# 12V.net
KiCad netlist of a schematic drawn in Altium Designer
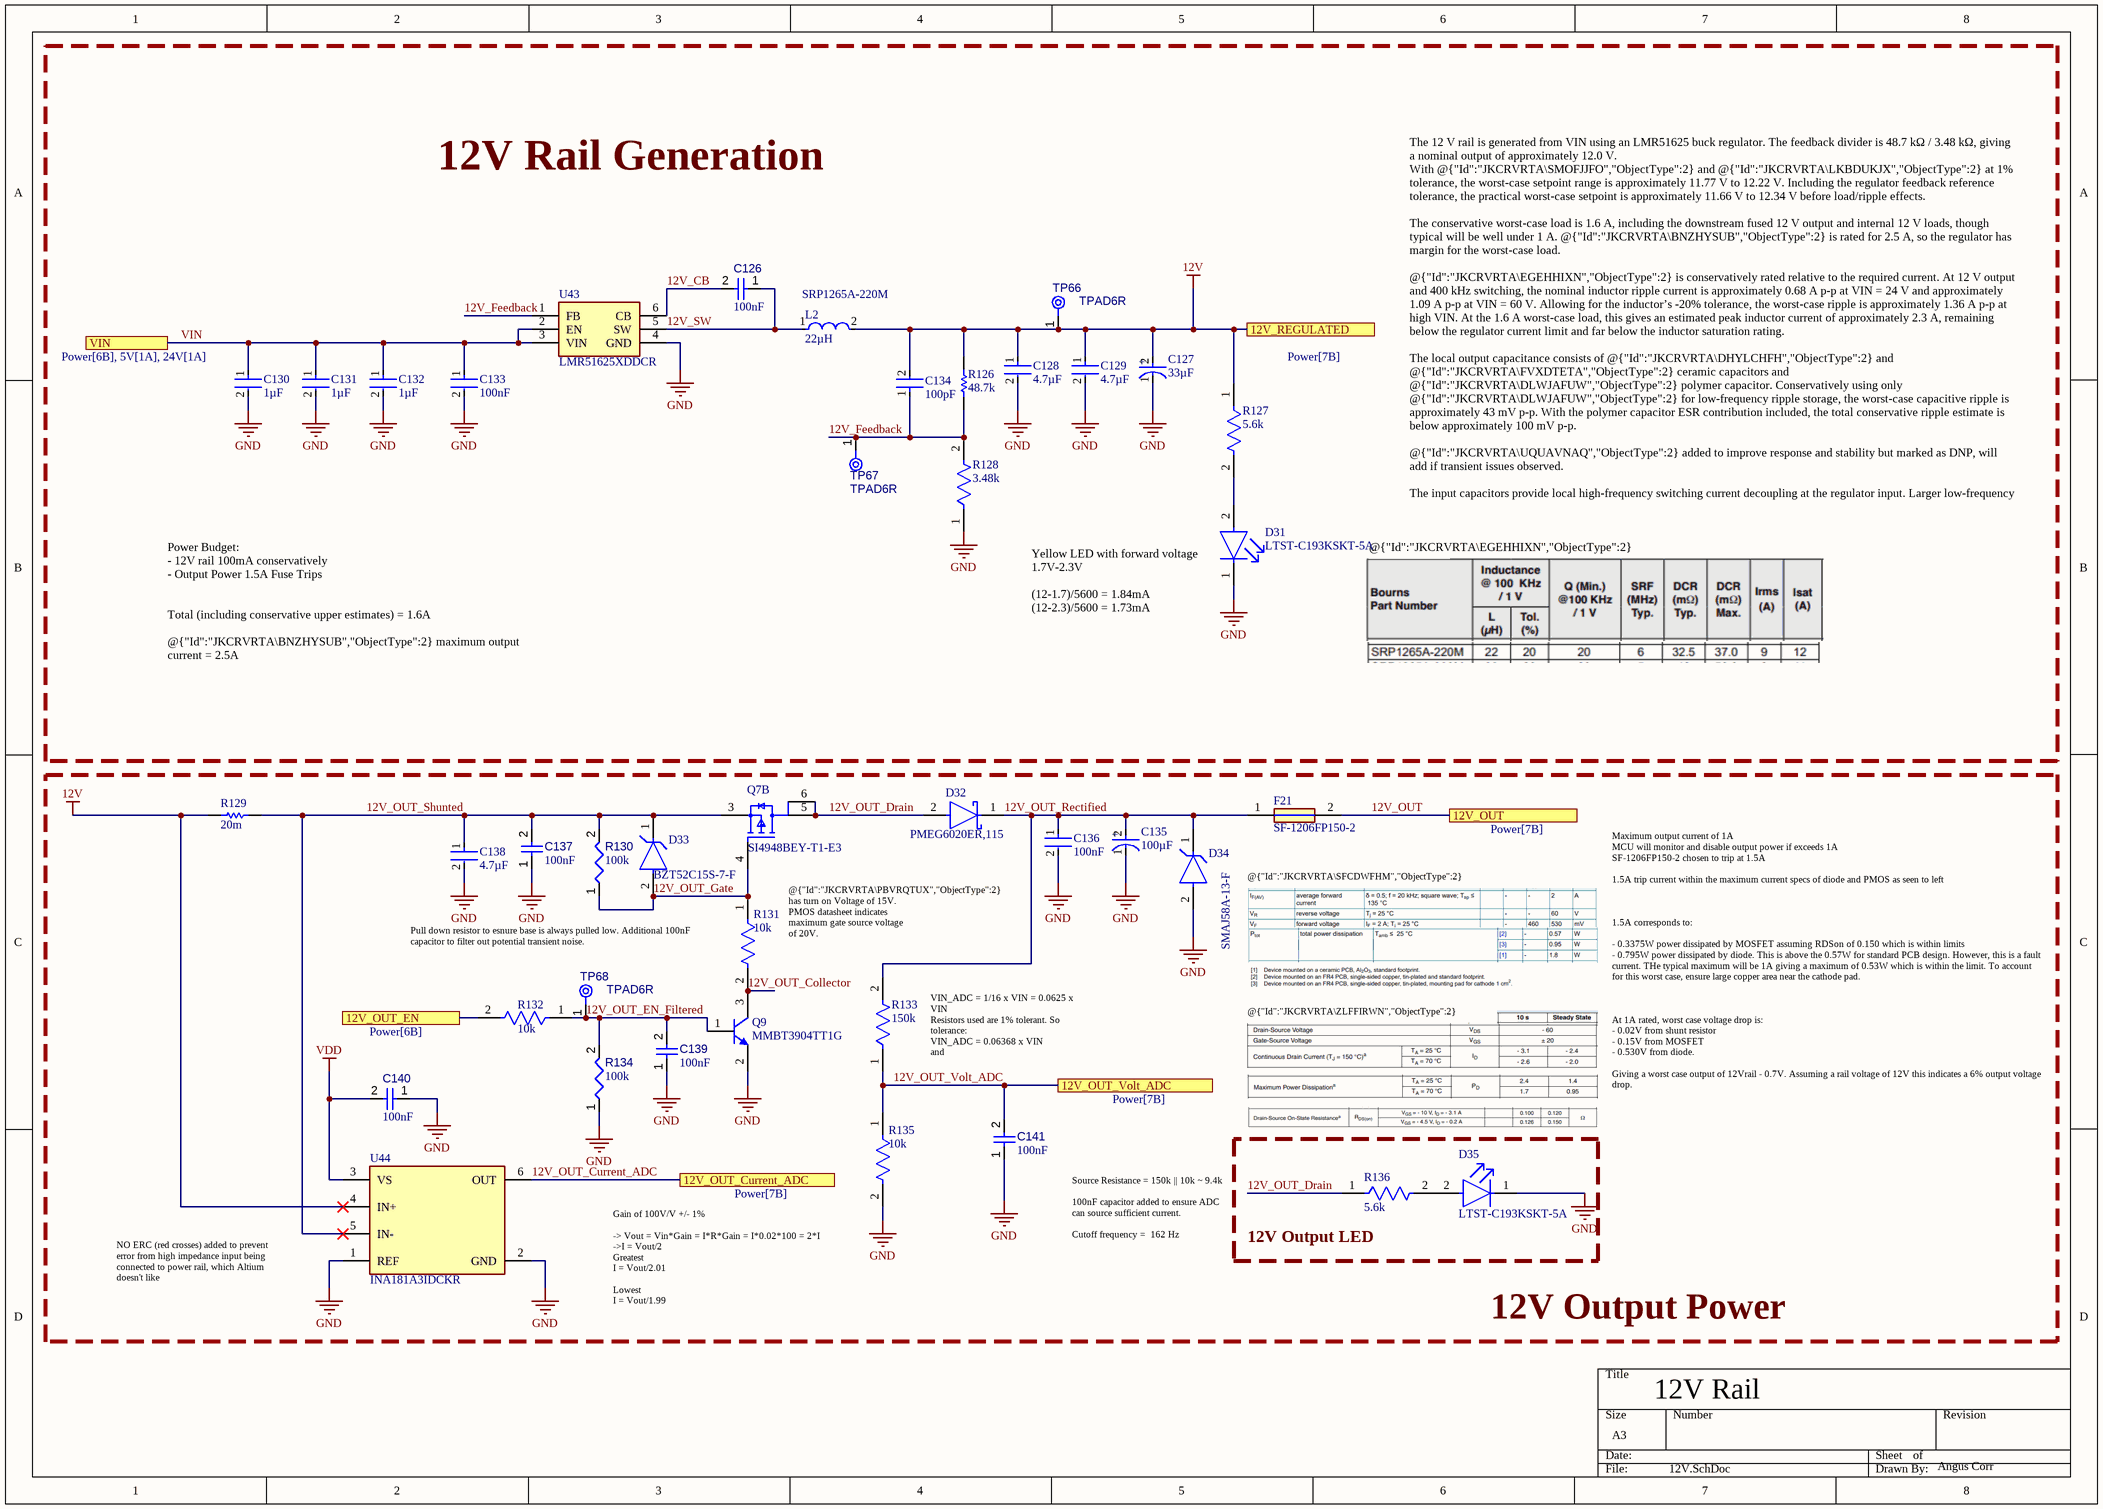
[diagram p0:  12V.SchDoc]

(export (version "E")
  (design (tool "Eeschema 10.0.6"))
  (components
    (comp (ref "C126")
      (value "100nF")
      (footprint "CAPC1608X90X40NL10T20")
      (description "Chip Capacitor, 100 nF, +/- 10%, 50 V, 0603 (1608 Metric)")
      (fields (field (name "TOLERANCE") "10%") (field (name "Comment") "Capacitor 100 nF +/-10% 50 V 0603"))
      (libsource (lib "HIL RIG FYP") (part "CAP-NP-2"))
    )
    (comp (ref "C127")
      (value "33µF")
      (footprint "FP-EEH-D8-MFG")
      (description "Cap Aluminum 33uF 50V 20% (6.3 X 7.7mm) SMD 0.04 Ohm 1600mA 5000 hr 105°C Embossed T/R")
      (fields (field (name "TOLERANCE") "20%") (field (name "Comment") "EEHZA1H330XP"))
      (libsource (lib "HIL RIG FYP") (part "a00bbbee19879c290e62620ae7e47b1"))
    )
    (comp (ref "C128")
      (value "4.7µF")
      (footprint "FP-GRM21B-0_2-e0_2_0_7-MFG")
      (description "50V 4.7uF X7R ±10% 0805 Multilayer Ceramic Capacitors MLCC - SMD/SMT ROHS")
      (fields (field (name "TOLERANCE") "10%") (field (name "Comment") "GRM21BZ71H475KE15L"))
      (libsource (lib "HIL RIG FYP") (part "b4654b650e69147ec39a6b967a45e02"))
    )
    (comp (ref "C129")
      (value "4.7µF")
      (footprint "FP-GRM21B-0_2-e0_2_0_7-MFG")
      (description "50V 4.7uF X7R ±10% 0805 Multilayer Ceramic Capacitors MLCC - SMD/SMT ROHS")
      (fields (field (name "TOLERANCE") "10%") (field (name "Comment") "GRM21BZ71H475KE15L"))
      (libsource (lib "HIL RIG FYP") (part "b4654b650e69147ec39a6b967a45e02"))
    )
    (comp (ref "C130")
      (value "1µF")
      (footprint "FP-GRJ21B-0_35-MFG")
      (description "100V 1uF X7S ±10% 0805 Multilayer Ceramic Capacitors MLCC - SMD/SMT ROHS")
      (fields (field (name "TOLERANCE") "10%") (field (name "Comment") "GRJ21BC72A105KE11L"))
      (libsource (lib "HIL RIG FYP") (part "b4654b650e69147ec39a6b967a45e02"))
    )
    (comp (ref "C131")
      (value "1µF")
      (footprint "FP-GRJ21B-0_35-MFG")
      (description "100V 1uF X7S ±10% 0805 Multilayer Ceramic Capacitors MLCC - SMD/SMT ROHS")
      (fields (field (name "TOLERANCE") "10%") (field (name "Comment") "GRJ21BC72A105KE11L"))
      (libsource (lib "HIL RIG FYP") (part "b4654b650e69147ec39a6b967a45e02"))
    )
    (comp (ref "C132")
      (value "1µF")
      (footprint "FP-GRJ21B-0_35-MFG")
      (description "100V 1uF X7S ±10% 0805 Multilayer Ceramic Capacitors MLCC - SMD/SMT ROHS")
      (fields (field (name "TOLERANCE") "10%") (field (name "Comment") "GRJ21BC72A105KE11L"))
      (libsource (lib "HIL RIG FYP") (part "b4654b650e69147ec39a6b967a45e02"))
    )
    (comp (ref "C133")
      (value "100nF")
      (footprint "FP-GRM31C-0_2-e0_3_0_8-IPC_C")
      (description "100V 100nF C0G ±5% 1206 Multilayer Ceramic Capacitors MLCC - SMD/SMT ROHS")
      (fields (field (name "TOLERANCE") "5%") (field (name "Comment") "GRM31C5C2A104JA01L"))
      (libsource (lib "HIL RIG FYP") (part "02cd4be3c70576c341d710602a673aa"))
    )
    (comp (ref "C134")
      (value "100pF")
      (footprint "FP-C0603C-CF-IPC_B")
      (description "Multilayer Ceramic Capacitors MLCC - SMD/SMT 50V 100pF X8R 0603 1%")
      (fields (field (name "Comment") "C0603C101F5HACTU"))
      (libsource (lib "HIL RIG FYP") (part "b4654b650e69147ec39a6b967a45e02"))
    )
    (comp (ref "C135")
      (value "100µF")
      (footprint "FP-MVYAKE0-MFG")
      (description "Cap Aluminum 100uF 100V 20% (12.5 X 13.5mm) SMD 450mA 5000h 105°C T/R")
      (fields (field (name "TOLERANCE") "20%") (field (name "Comment") "EMVY101ARA101MKE0S"))
      (libsource (lib "HIL RIG FYP") (part "203bc49f2ac43e59fd269a8c329ed05"))
    )
    (comp (ref "C136")
      (value "100nF")
      (footprint "FP-GRM31C-0_2-e0_3_0_8-IPC_C")
      (description "100V 100nF C0G ±5% 1206 Multilayer Ceramic Capacitors MLCC - SMD/SMT ROHS")
      (fields (field (name "TOLERANCE") "5%") (field (name "Comment") "GRM31C5C2A104JA01L"))
      (libsource (lib "HIL RIG FYP") (part "02cd4be3c70576c341d710602a673aa"))
    )
    (comp (ref "C137")
      (value "100nF")
      (footprint "CAPC1608X90X40NL10T20")
      (description "Chip Capacitor, 100 nF, +/- 10%, 50 V, 0603 (1608 Metric)")
      (fields (field (name "TOLERANCE") "10%") (field (name "Comment") "Capacitor 100 nF +/-10% 50 V 0603"))
      (libsource (lib "HIL RIG FYP") (part "CAP-NP-2"))
    )
    (comp (ref "C138")
      (value "4.7µF")
      (footprint "FP-GRM21B-0_2-e0_2_0_7-MFG")
      (description "50V 4.7uF X7R ±10% 0805 Multilayer Ceramic Capacitors MLCC - SMD/SMT ROHS")
      (fields (field (name "TOLERANCE") "10%") (field (name "Comment") "GRM21BZ71H475KE15L"))
      (libsource (lib "HIL RIG FYP") (part "b4654b650e69147ec39a6b967a45e02"))
    )
    (comp (ref "C139")
      (value "100nF")
      (footprint "CAPC1608X90X40NL10T20")
      (description "Chip Capacitor, 100 nF, +/- 10%, 50 V, 0603 (1608 Metric)")
      (fields (field (name "TOLERANCE") "10%") (field (name "Comment") "Capacitor 100 nF +/-10% 50 V 0603"))
      (libsource (lib "HIL RIG FYP") (part "CAP-NP-2"))
    )
    (comp (ref "C140")
      (value "100nF")
      (footprint "CAPC1608X90X40NL10T20")
      (description "Chip Capacitor, 100 nF, +/- 10%, 50 V, 0603 (1608 Metric)")
      (fields (field (name "TOLERANCE") "10%") (field (name "Comment") "Capacitor 100 nF +/-10% 50 V 0603"))
      (libsource (lib "HIL RIG FYP") (part "CAP-NP-2"))
    )
    (comp (ref "C141")
      (value "100nF")
      (footprint "CAPC1608X90X40NL10T20")
      (description "Chip Capacitor, 100 nF, +/- 10%, 50 V, 0603 (1608 Metric)")
      (fields (field (name "TOLERANCE") "10%") (field (name "Comment") "Capacitor 100 nF +/-10% 50 V 0603"))
      (libsource (lib "HIL RIG FYP") (part "CAP-NP-2"))
    )
    (comp (ref "D31")
      (value "LTST-C193KSKT-5A")
      (footprint "FP-LTST-C193KGKT-5A-MFG")
      (description "LED yellow 0603 wavelength 587~594.5nm light intensity 7.1~45mcd Front Mounting")
      (libsource (lib "HIL RIG FYP") (part "8706943c75ba83719d021d2fdc84c58"))
    )
    (comp (ref "D32")
      (value "PMEG6020ER,115")
      (footprint "FP-SOD123W-MFG")
      (description "PMEG6020 Series 60 V 2 A SMT Llow VF MEGA Schottky Barrier Rectifier - SOD-123W")
      (libsource (lib "HIL RIG FYP") (part "1d6ec82d83fb6aee721767c19dac4b9"))
    )
    (comp (ref "D33")
      (value "BZT52C15S-7-F")
      (footprint "FP-SOD323-IPC_A")
      (description "BZT52C15S Series 200 mW 15 V 10 mA Surface Mount Zener Diode - SOD-323")
      (libsource (lib "HIL RIG FYP") (part "f813f71cba58e380607f5dd3caf9714"))
    )
    (comp (ref "D34")
      (value "SMAJ58A-13-F")
      (footprint "FP-SMA-MFG")
      (description "SMAJ Series 58 V 400 W SMT Uni-Directional TVS Diode - DO-214AC")
      (libsource (lib "HIL RIG FYP") (part "f813f71cba58e380607f5dd3caf9714"))
    )
    (comp (ref "D35")
      (value "LTST-C193KSKT-5A")
      (footprint "FP-LTST-C193KGKT-5A-MFG")
      (description "LED yellow 0603 wavelength 587~594.5nm light intensity 7.1~45mcd Front Mounting")
      (libsource (lib "HIL RIG FYP") (part "8706943c75ba83719d021d2fdc84c58"))
    )
    (comp (ref "F21")
      (value "SF-1206FP150-2")
      (footprint "FUSC3116X70N")
      (description "Surface Mount Fuses 1.5A Fast Acting 1206 Singlfuse")
      (fields (field (name "MOUSER PART NUMBER") "652-SF-1206FP150-2"))
      (libsource (lib "HIL RIG FYP") (part "SF-1206FP150-2"))
    )
    (comp (ref "L2")
      (value "22µH")
      (footprint "FP-SRP1265A-MFG")
      (fields (field (name "TOLERANCE") "20%") (field (name "Comment") "SRP1265A-220M"))
      (libsource (lib "HIL RIG FYP") (part "725321dda6339637d4d059423bc1c3c"))
    )
    (comp (ref "Q7")
      (value "SI4948BEY-T1-E3")
      (footprint "FP-C-06527-IPC_B")
      (description "Dual P-Channel 60 V 0.12 Ohms Surface Mount Power Mosfet - SOIC-8")
      (libsource (lib "HIL RIG FYP") (part "8dc75c867fb8938c255332086adbf49"))
    )
    (comp (ref "Q9")
      (value "MMBT3904TT1G")
      (footprint "ONSC-SC-75-3-463-01_V")
      (description "on Semi MMBT3904TT1G NPN Bipolar Transistor, 0.2 A, 40 V, 3-PIN SOT-416")
      (libsource (lib "HIL RIG FYP") (part "ONSC-NPN-B1E2C3-3"))
    )
    (comp (ref "R126")
      (value "48.7k")
      (footprint "RESC1608X55X25ML10T15")
      (description "Res Thick Film 0603 48.7K Ohm 1% 0.1W(1/10W) ±100ppm/C Pad SMD T/R")
      (fields (field (name "TOLERANCE") "1%") (field (name "Comment") "RC0603FR-0748K7L"))
      (libsource (lib "HIL RIG FYP") (part "RES"))
    )
    (comp (ref "R127")
      (value "5.6k")
      (footprint "FP-RT0603-IPC_C")
      (description "Fixed Resistor, Thin Film, 0.1W, 5600ohm, 75V, 1% +/-Tol, 50ppm/Cel, Surface Mount, 0603")
      (fields (field (name "TOLERANCE") "1%") (field (name "Comment") "RT0603FRE075K6L"))
      (libsource (lib "HIL RIG FYP") (part "1029c3af85768c4190bb7ad29bc67b5"))
    )
    (comp (ref "R128")
      (value "3.48k")
      (footprint "FP-AC0603-IPC_C")
      (description "Res Thick Film 0603 3.48K Ohm 1% 0.1W(1/10W) ±100ppm/C Pad SMD T/R Automotive AEC-Q200")
      (fields (field (name "TOLERANCE") "1%") (field (name "Comment") "AC0603FR-073K48L"))
      (libsource (lib "HIL RIG FYP") (part "1029c3af85768c4190bb7ad29bc67b5"))
    )
    (comp (ref "R129")
      (value "20m")
      (footprint "RESC3216X89X51NL25T25")
      (description "Res Metal Strip 1206 0.02 Ohm 1% 1/4W ±75ppm/°C Molded SMD SMD Embossed Plastic T/R")
      (fields (field (name "TOLERANCE") "1%") (field (name "Comment") "WSL1206R0200FEA"))
      (libsource (lib "HIL RIG FYP") (part "RES"))
    )
    (comp (ref "R130")
      (value "100k")
      (footprint "FP-AC0603-IPC_C")
      (description "Res Thick Film 0603 100K Ohm 1% 0.1W(1/10W) ±100ppm/C Pad SMD T/R Automotive")
      (fields (field (name "TOLERANCE") "1%") (field (name "Comment") "AC0603FR-07100KL"))
      (libsource (lib "HIL RIG FYP") (part "RES-2"))
    )
    (comp (ref "R131")
      (value "10k")
      (footprint "FP-RT0603-IPC_C")
      (description "Res Thin Film 0603 10K Ohm 0.1% 1/10W ¦25ppm/¦C SMD Paper T/R")
      (fields (field (name "TOLERANCE") "0.1%") (field (name "Comment") "RT0603BRD0710KL"))
      (libsource (lib "HIL RIG FYP") (part "1029c3af85768c4190bb7ad29bc67b5"))
    )
    (comp (ref "R132")
      (value "10k")
      (footprint "FP-RT0603-IPC_C")
      (description "Res Thin Film 0603 10K Ohm 0.1% 1/10W ¦25ppm/¦C SMD Paper T/R")
      (fields (field (name "TOLERANCE") "0.1%") (field (name "Comment") "RT0603BRD0710KL"))
      (libsource (lib "HIL RIG FYP") (part "1029c3af85768c4190bb7ad29bc67b5"))
    )
    (comp (ref "R133")
      (value "150k")
      (footprint "FP-CRGCQ0603-IPC_A")
      (description "Res Thick Film 0603 150K Ohm 1% 0.1W(1/10W) ±100ppm/C Pad SMD Automotive T/R")
      (fields (field (name "TOLERANCE") "1%") (field (name "Comment") "CRGCQ0603F150K"))
      (libsource (lib "HIL RIG FYP") (part "1029c3af85768c4190bb7ad29bc67b5"))
    )
    (comp (ref "R134")
      (value "100k")
      (footprint "FP-AC0603-IPC_C")
      (description "Res Thick Film 0603 100K Ohm 1% 0.1W(1/10W) ±100ppm/C Pad SMD T/R Automotive")
      (fields (field (name "TOLERANCE") "1%") (field (name "Comment") "AC0603FR-07100KL"))
      (libsource (lib "HIL RIG FYP") (part "RES-2"))
    )
    (comp (ref "R135")
      (value "10k")
      (footprint "FP-RT0603-IPC_C")
      (description "Res Thin Film 0603 10K Ohm 0.1% 1/10W ¦25ppm/¦C SMD Paper T/R")
      (fields (field (name "TOLERANCE") "0.1%") (field (name "Comment") "RT0603BRD0710KL"))
      (libsource (lib "HIL RIG FYP") (part "1029c3af85768c4190bb7ad29bc67b5"))
    )
    (comp (ref "R136")
      (value "5.6k")
      (footprint "FP-RT0603-IPC_C")
      (description "Fixed Resistor, Thin Film, 0.1W, 5600ohm, 75V, 1% +/-Tol, 50ppm/Cel, Surface Mount, 0603")
      (fields (field (name "TOLERANCE") "1%") (field (name "Comment") "RT0603FRE075K6L"))
      (libsource (lib "HIL RIG FYP") (part "1029c3af85768c4190bb7ad29bc67b5"))
    )
    (comp (ref "TP66")
      (value "TPAD6R")
      (footprint "TP06R")
      (description "0.6mm round")
      (libsource (lib "HIL RIG FYP") (part "CMP-001-0001-4"))
    )
    (comp (ref "TP67")
      (value "TPAD6R")
      (footprint "TP06R")
      (description "0.6mm round")
      (libsource (lib "HIL RIG FYP") (part "CMP-001-0001-4"))
    )
    (comp (ref "TP68")
      (value "TPAD6R")
      (footprint "TP06R")
      (description "0.6mm round")
      (libsource (lib "HIL RIG FYP") (part "CMP-001-0001-4"))
    )
    (comp (ref "U43")
      (value "LMR51625XDDCR")
      (footprint "SOT95P280X110-6N")
      (description "Switching Voltage Regulators SIMPLE SWITCHER synchronous buck converter with 4.3V-to-60V")
      (fields (field (name "MOUSER PART NUMBER") "595-LMR51625XDDCR"))
      (libsource (lib "HIL RIG FYP") (part "LMR51625XDDCR"))
    )
    (comp (ref "U44")
      (value "INA181A3IDCKR")
      (footprint "FP-DCK0006A-IPC_A")
      (description "26-V bi-directional 350-kHz current-sense amplifier 6-SC70 -40 to 125")
      (libsource (lib "HIL RIG FYP") (part "a7b5cee9b6bc60f4871af0ee2c3b109"))
    )
  )
  (nets
    (net (code "1") (name "/12V_CB") (class "Default")
      (node (ref "C126") (pin "2") (pinfunction "2_2") (pintype "passive"))
      (node (ref "U43") (pin "6") (pinfunction "CB_6") (pintype "passive"))
    )
    (net (code "2") (name "/12V_Feedback") (class "Default")
      (node (ref "C134") (pin "1") (pinfunction "1_1") (pintype "passive"))
      (node (ref "R126") (pin "1") (pinfunction "1_1") (pintype "passive"))
      (node (ref "R128") (pin "2") (pinfunction "2_2") (pintype "passive"))
      (node (ref "TP67") (pin "1") (pinfunction "TP_1") (pintype "passive"))
      (node (ref "U43") (pin "1") (pinfunction "FB_1") (pintype "passive"))
    )
    (net (code "3") (name "/12V_OUT") (class "Default")
      (node (ref "F21") (pin "2") (pinfunction "2_2") (pintype "passive"))
    )
    (net (code "4") (name "/12V_OUT_Collector") (class "Default")
      (node (ref "Q9") (pin "3") (pinfunction "C_3") (pintype "passive"))
      (node (ref "R131") (pin "2") (pinfunction "2_2") (pintype "passive"))
    )
    (net (code "5") (name "/12V_OUT_Current_ADC") (class "Default")
      (node (ref "U44") (pin "6") (pinfunction "OUT_6") (pintype "passive"))
    )
    (net (code "6") (name "/12V_OUT_Drain") (class "Default")
      (node (ref "D32") (pin "2") (pinfunction "A_2") (pintype "passive"))
      (node (ref "Q7") (pin "5") (pinfunction "D2_5") (pintype "passive"))
      (node (ref "Q7") (pin "6") (pinfunction "D2_6") (pintype "passive"))
      (node (ref "R136") (pin "1") (pinfunction "1_1") (pintype "passive"))
    )
    (net (code "7") (name "/12V_OUT_EN") (class "Default")
      (node (ref "R132") (pin "2") (pinfunction "2_2") (pintype "passive"))
    )
    (net (code "8") (name "/12V_OUT_EN_Filtered") (class "Default")
      (node (ref "C139") (pin "2") (pinfunction "2_2") (pintype "passive"))
      (node (ref "Q9") (pin "1") (pinfunction "B_1") (pintype "passive"))
      (node (ref "R132") (pin "1") (pinfunction "1_1") (pintype "passive"))
      (node (ref "R134") (pin "2") (pinfunction "2_2") (pintype "passive"))
      (node (ref "TP68") (pin "1") (pinfunction "TP_1") (pintype "passive"))
    )
    (net (code "9") (name "/12V_OUT_Gate") (class "Default")
      (node (ref "D33") (pin "2") (pinfunction "A_2") (pintype "passive"))
      (node (ref "Q7") (pin "4") (pinfunction "G2_4") (pintype "passive"))
      (node (ref "R130") (pin "1") (pinfunction "1_1") (pintype "passive"))
      (node (ref "R131") (pin "1") (pinfunction "1_1") (pintype "passive"))
    )
    (net (code "10") (name "/12V_OUT_Rectified") (class "Default")
      (node (ref "C135") (pin "2") (pinfunction "A_2") (pintype "passive"))
      (node (ref "C136") (pin "1") (pinfunction "1_1") (pintype "passive"))
      (node (ref "D32") (pin "1") (pinfunction "C_1") (pintype "passive"))
      (node (ref "D34") (pin "1") (pinfunction "C_1") (pintype "passive"))
      (node (ref "F21") (pin "1") (pinfunction "1_1") (pintype "passive"))
      (node (ref "R133") (pin "2") (pinfunction "2_2") (pintype "passive"))
    )
    (net (code "11") (name "/12V_OUT_Shunted") (class "Default")
      (node (ref "C137") (pin "2") (pinfunction "2_2") (pintype "passive"))
      (node (ref "C138") (pin "1") (pinfunction "1_1") (pintype "passive"))
      (node (ref "D33") (pin "1") (pinfunction "C_1") (pintype "passive"))
      (node (ref "Q7") (pin "3") (pinfunction "S2_3") (pintype "passive"))
      (node (ref "R129") (pin "2") (pinfunction "2_2") (pintype "passive"))
      (node (ref "R130") (pin "2") (pinfunction "2_2") (pintype "passive"))
      (node (ref "U44") (pin "5") (pinfunction "IN-_5") (pintype "tri_state"))
    )
    (net (code "12") (name "/12V_OUT_Volt_ADC") (class "Default")
      (node (ref "C141") (pin "2") (pinfunction "2_2") (pintype "passive"))
      (node (ref "R133") (pin "1") (pinfunction "1_1") (pintype "passive"))
      (node (ref "R135") (pin "1") (pinfunction "1_1") (pintype "passive"))
    )
    (net (code "13") (name "/12V_SW") (class "Default")
      (node (ref "C126") (pin "1") (pinfunction "1_1") (pintype "passive"))
      (node (ref "L2") (pin "1") (pinfunction "1_1") (pintype "passive"))
      (node (ref "U43") (pin "5") (pinfunction "SW_5") (pintype "passive"))
    )
    (net (code "14") (name "/VIN") (class "Default")
      (node (ref "C130") (pin "1") (pinfunction "1_1") (pintype "passive"))
      (node (ref "C131") (pin "1") (pinfunction "1_1") (pintype "passive"))
      (node (ref "C132") (pin "1") (pinfunction "1_1") (pintype "passive"))
      (node (ref "C133") (pin "1") (pinfunction "1_1") (pintype "passive"))
      (node (ref "U43") (pin "2") (pinfunction "EN_2") (pintype "passive"))
      (node (ref "U43") (pin "3") (pinfunction "VIN_3") (pintype "passive"))
    )
    (net (code "15") (name "12V") (class "Default")
      (node (ref "C127") (pin "2") (pinfunction "A_2") (pintype "passive"))
      (node (ref "C128") (pin "1") (pinfunction "1_1") (pintype "passive"))
      (node (ref "C129") (pin "1") (pinfunction "1_1") (pintype "passive"))
      (node (ref "C134") (pin "2") (pinfunction "2_2") (pintype "passive"))
      (node (ref "L2") (pin "2") (pinfunction "2_2") (pintype "passive"))
      (node (ref "R126") (pin "2") (pinfunction "2_2") (pintype "passive"))
      (node (ref "R127") (pin "1") (pinfunction "1_1") (pintype "passive"))
      (node (ref "R129") (pin "1") (pinfunction "1_1") (pintype "passive"))
      (node (ref "TP66") (pin "1") (pinfunction "TP_1") (pintype "passive"))
      (node (ref "U44") (pin "4") (pinfunction "IN+_4") (pintype "tri_state"))
    )
    (net (code "16") (name "GND") (class "Default")
      (node (ref "C127") (pin "1") (pinfunction "C_1") (pintype "passive"))
      (node (ref "C128") (pin "2") (pinfunction "2_2") (pintype "passive"))
      (node (ref "C129") (pin "2") (pinfunction "2_2") (pintype "passive"))
      (node (ref "C130") (pin "2") (pinfunction "2_2") (pintype "passive"))
      (node (ref "C131") (pin "2") (pinfunction "2_2") (pintype "passive"))
      (node (ref "C132") (pin "2") (pinfunction "2_2") (pintype "passive"))
      (node (ref "C133") (pin "2") (pinfunction "2_2") (pintype "passive"))
      (node (ref "C135") (pin "1") (pinfunction "C_1") (pintype "passive"))
      (node (ref "C136") (pin "2") (pinfunction "2_2") (pintype "passive"))
      (node (ref "C137") (pin "1") (pinfunction "1_1") (pintype "passive"))
      (node (ref "C138") (pin "2") (pinfunction "2_2") (pintype "passive"))
      (node (ref "C139") (pin "1") (pinfunction "1_1") (pintype "passive"))
      (node (ref "C140") (pin "1") (pinfunction "1_1") (pintype "passive"))
      (node (ref "C141") (pin "1") (pinfunction "1_1") (pintype "passive"))
      (node (ref "D31") (pin "1") (pinfunction "C_1") (pintype "passive"))
      (node (ref "D34") (pin "2") (pinfunction "A_2") (pintype "passive"))
      (node (ref "D35") (pin "1") (pinfunction "C_1") (pintype "passive"))
      (node (ref "Q9") (pin "2") (pinfunction "E_2") (pintype "passive"))
      (node (ref "R128") (pin "1") (pinfunction "1_1") (pintype "passive"))
      (node (ref "R134") (pin "1") (pinfunction "1_1") (pintype "passive"))
      (node (ref "R135") (pin "2") (pinfunction "2_2") (pintype "passive"))
      (node (ref "U43") (pin "4") (pinfunction "GND_4") (pintype "passive"))
      (node (ref "U44") (pin "1") (pinfunction "REF_1") (pintype "passive"))
      (node (ref "U44") (pin "2") (pinfunction "GND_2") (pintype "power_in"))
    )
    (net (code "17") (name "Net-(D31-A)") (class "Default")
      (node (ref "D31") (pin "2") (pinfunction "A_2") (pintype "passive"))
      (node (ref "R127") (pin "2") (pinfunction "2_2") (pintype "passive"))
    )
    (net (code "18") (name "Net-(D35-A)") (class "Default")
      (node (ref "D35") (pin "2") (pinfunction "A_2") (pintype "passive"))
      (node (ref "R136") (pin "2") (pinfunction "2_2") (pintype "passive"))
    )
    (net (code "19") (name "VDD") (class "Default")
      (node (ref "C140") (pin "2") (pinfunction "2_2") (pintype "passive"))
      (node (ref "U44") (pin "3") (pinfunction "VS_3") (pintype "power_in"))
    )
  )
)
